# BPQ.net
KiCad netlist of a schematic drawn in Altium Designer
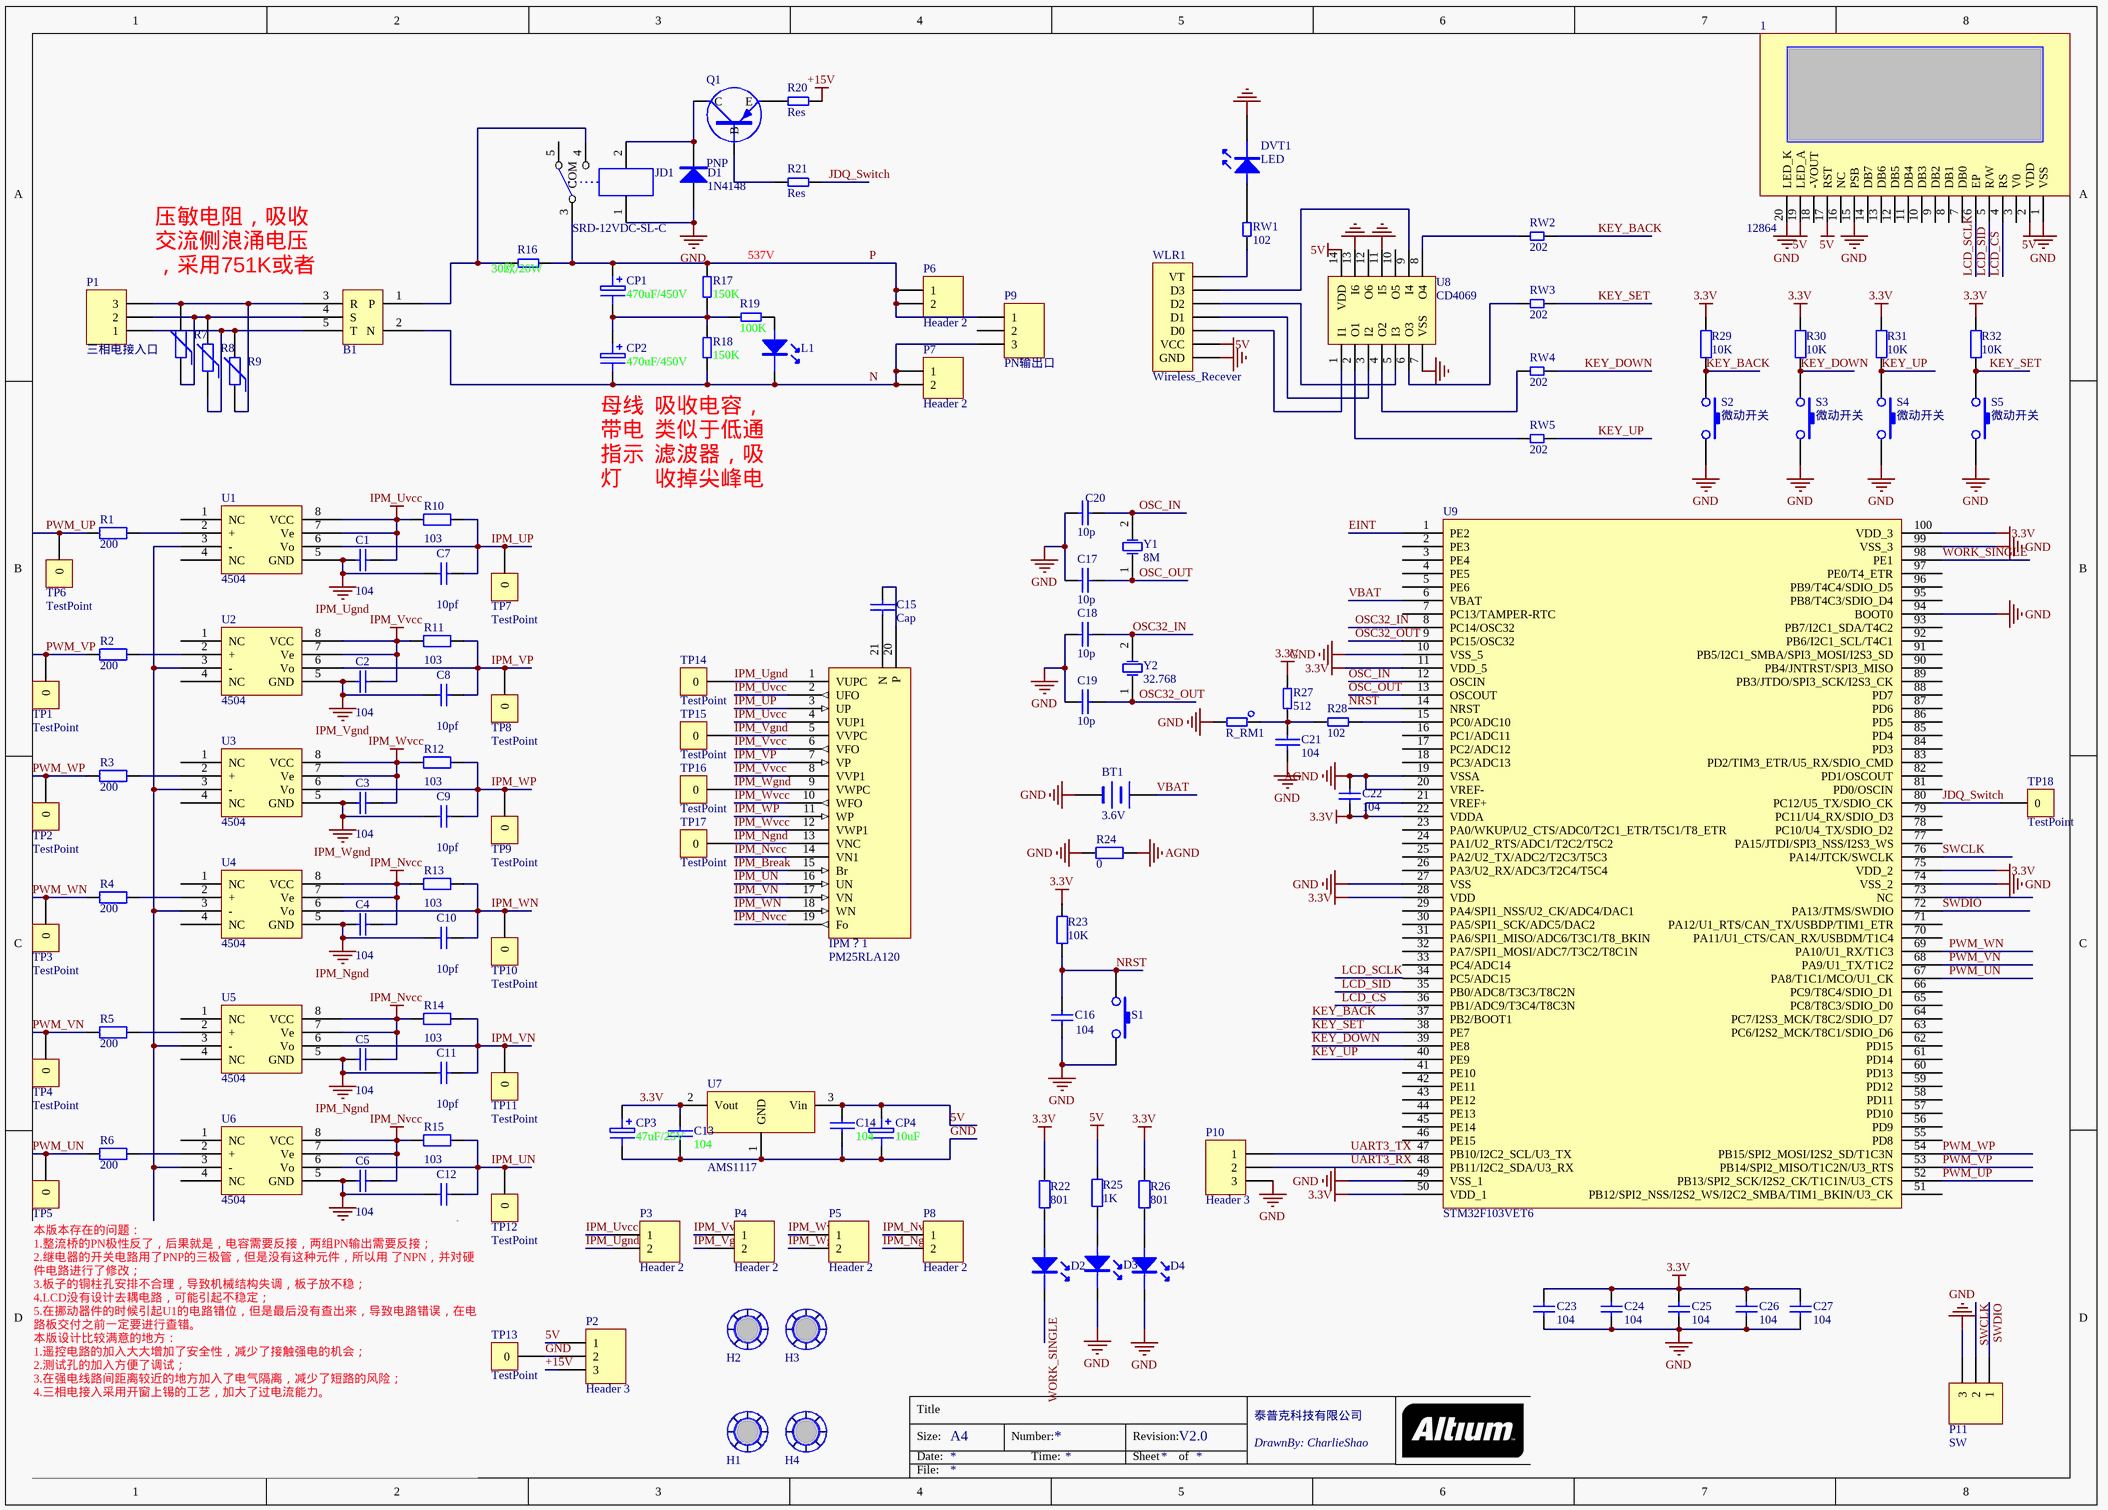
[diagram p0: BPQ.SchDoc]

(export (version "E")
  (design (tool "Eeschema 10.0.6"))
  (components
    (comp (ref "1") (value "12864") (footprint "YX12864B") (libsource (lib "Backup of 杨飞原理库") (part "12864")))
    (comp (ref "B1")
      (value "3BRIDGE")
      (footprint "cloudlib:三相整流桥")
      (libsource (lib "cloudlib") (part "三相整流桥"))
    )
    (comp (ref "BT1")
      (value "3.6V")
      (footprint "CR1220")
      (description "3.6V纽扣电池")
      (libsource (lib "cloudlib") (part "BATTERY"))
    )
    (comp (ref "C1")
      (value "104")
      (footprint "0805C")
      (description "Capacitor")
      (fields (field (name "Comment") "Cap") (field (name "PUBLISHER") "Altium Limited"))
      (libsource (lib "Miscellaneous Devices") (part "Cap"))
    )
    (comp (ref "C2")
      (value "104")
      (footprint "0805C")
      (description "Capacitor")
      (fields (field (name "Comment") "Cap") (field (name "PUBLISHER") "Altium Limited"))
      (libsource (lib "Miscellaneous Devices") (part "Cap"))
    )
    (comp (ref "C3")
      (value "104")
      (footprint "0805C")
      (description "Capacitor")
      (fields (field (name "Comment") "Cap") (field (name "PUBLISHER") "Altium Limited"))
      (libsource (lib "Miscellaneous Devices") (part "Cap"))
    )
    (comp (ref "C4")
      (value "104")
      (footprint "0805C")
      (description "Capacitor")
      (fields (field (name "Comment") "Cap") (field (name "PUBLISHER") "Altium Limited"))
      (libsource (lib "Miscellaneous Devices") (part "Cap"))
    )
    (comp (ref "C5")
      (value "104")
      (footprint "0805C")
      (description "Capacitor")
      (fields (field (name "Comment") "Cap") (field (name "PUBLISHER") "Altium Limited"))
      (libsource (lib "Miscellaneous Devices") (part "Cap"))
    )
    (comp (ref "C6")
      (value "104")
      (footprint "0805C")
      (description "Capacitor")
      (fields (field (name "Comment") "Cap") (field (name "PUBLISHER") "Altium Limited"))
      (libsource (lib "Miscellaneous Devices") (part "Cap"))
    )
    (comp (ref "C7")
      (value "10pf")
      (footprint "0805C")
      (description "Capacitor")
      (fields (field (name "Comment") "Cap") (field (name "PUBLISHER") "Altium Limited"))
      (libsource (lib "Miscellaneous Devices") (part "Cap"))
    )
    (comp (ref "C8")
      (value "10pf")
      (footprint "0805C")
      (description "Capacitor")
      (fields (field (name "Comment") "Cap") (field (name "PUBLISHER") "Altium Limited"))
      (libsource (lib "Miscellaneous Devices") (part "Cap"))
    )
    (comp (ref "C9")
      (value "10pf")
      (footprint "0805C")
      (description "Capacitor")
      (fields (field (name "Comment") "Cap") (field (name "PUBLISHER") "Altium Limited"))
      (libsource (lib "Miscellaneous Devices") (part "Cap"))
    )
    (comp (ref "C10")
      (value "10pf")
      (footprint "0805C")
      (description "Capacitor")
      (fields (field (name "Comment") "Cap") (field (name "PUBLISHER") "Altium Limited"))
      (libsource (lib "Miscellaneous Devices") (part "Cap"))
    )
    (comp (ref "C11")
      (value "10pf")
      (footprint "0805C")
      (description "Capacitor")
      (fields (field (name "Comment") "Cap") (field (name "PUBLISHER") "Altium Limited"))
      (libsource (lib "Miscellaneous Devices") (part "Cap"))
    )
    (comp (ref "C12")
      (value "10pf")
      (footprint "0805C")
      (description "Capacitor")
      (fields (field (name "Comment") "Cap") (field (name "PUBLISHER") "Altium Limited"))
      (libsource (lib "Miscellaneous Devices") (part "Cap"))
    )
    (comp (ref "C13")
      (value "104")
      (footprint "0805C")
      (description "非极性电容")
      (libsource (lib "cloudlib") (part "Cap"))
    )
    (comp (ref "C14")
      (value "104")
      (footprint "0805C")
      (description "非极性电容")
      (libsource (lib "cloudlib") (part "Cap"))
    )
    (comp (ref "C15")
      (value "Cap")
      (footprint "cloudlib:Cap_X")
      (description "非极性电容")
      (libsource (lib "cloudlib") (part "Cap"))
    )
    (comp (ref "C16")
      (value "104")
      (footprint "0805C")
      (description "Capacitor")
      (fields (field (name "PUBLISHER") "Altium Limited"))
      (libsource (lib "Miscellaneous Devices") (part "Cap"))
    )
    (comp (ref "C17")
      (value "10p")
      (footprint "0805C")
      (description "非极性电容")
      (libsource (lib "cloudlib") (part "Cap"))
    )
    (comp (ref "C18")
      (value "10p")
      (footprint "0805C")
      (description "非极性电容")
      (libsource (lib "cloudlib") (part "Cap"))
    )
    (comp (ref "C19")
      (value "10p")
      (footprint "0805C")
      (description "非极性电容")
      (libsource (lib "cloudlib") (part "Cap"))
    )
    (comp (ref "C20")
      (value "10p")
      (footprint "0805C")
      (description "非极性电容")
      (libsource (lib "cloudlib") (part "Cap"))
    )
    (comp (ref "C21")
      (value "104")
      (footprint "0805C")
      (description "非极性电容")
      (libsource (lib "cloudlib") (part "Cap"))
    )
    (comp (ref "C22")
      (value "104")
      (footprint "0805C")
      (description "Capacitor")
      (fields (field (name "PUBLISHER") "Altium Limited"))
      (libsource (lib "Miscellaneous Devices") (part "Cap"))
    )
    (comp (ref "C23")
      (value "104")
      (footprint "0805C")
      (description "Capacitor")
      (fields (field (name "PUBLISHER") "Altium Limited"))
      (libsource (lib "Miscellaneous Devices") (part "Cap"))
    )
    (comp (ref "C24")
      (value "104")
      (footprint "0805C")
      (description "Capacitor")
      (fields (field (name "PUBLISHER") "Altium Limited"))
      (libsource (lib "Miscellaneous Devices") (part "Cap"))
    )
    (comp (ref "C25")
      (value "104")
      (footprint "0805C")
      (description "Capacitor")
      (fields (field (name "PUBLISHER") "Altium Limited"))
      (libsource (lib "Miscellaneous Devices") (part "Cap"))
    )
    (comp (ref "C26")
      (value "104")
      (footprint "0805C")
      (description "Capacitor")
      (fields (field (name "PUBLISHER") "Altium Limited"))
      (libsource (lib "Miscellaneous Devices") (part "Cap"))
    )
    (comp (ref "C27")
      (value "104")
      (footprint "0805C")
      (description "Capacitor")
      (fields (field (name "PUBLISHER") "Altium Limited"))
      (libsource (lib "Miscellaneous Devices") (part "Cap"))
    )
    (comp (ref "CP1")
      (value "470uF/450V")
      (footprint "cloudlib:CAP_35X50")
      (description "极性电容")
      (libsource (lib "cloudlib") (part "Cap_Pol"))
    )
    (comp (ref "CP2")
      (value "470uF/450V")
      (footprint "cloudlib:CAP_35X50")
      (description "极性电容")
      (libsource (lib "cloudlib") (part "Cap_Pol"))
    )
    (comp (ref "CP3")
      (value "47uF/25V")
      (footprint "cloudlib:CAP_6.3X5.4")
      (description "极性电容")
      (libsource (lib "cloudlib") (part "Cap_Pol"))
    )
    (comp (ref "CP4")
      (value "10uF")
      (footprint "cloudlib:CAP_6.3X5.4")
      (description "极性电容")
      (libsource (lib "cloudlib") (part "Cap_Pol"))
    )
    (comp (ref "D1") (value "1N4148") (footprint "cloudlib:Diode_1206") (libsource (lib "*") (part "DIODE2")))
    (comp (ref "D2") (value "LED") (footprint "cloudlib:LED_0805") (libsource (lib "CCDXPLIB") (part "LED")))
    (comp (ref "D3") (value "LED") (footprint "cloudlib:LED_0805") (libsource (lib "CCDXPLIB") (part "LED")))
    (comp (ref "D4") (value "LED") (footprint "cloudlib:LED_0805") (libsource (lib "CCDXPLIB") (part "LED")))
    (comp (ref "DVT1") (value "LED") (footprint "cloudlib:LED_1206") (libsource (lib "*") (part "LED")))
    (comp (ref "H1") (value "铜柱孔") (footprint "HOLE") (libsource (lib "cloudlib") (part "铜柱孔")))
    (comp (ref "H2") (value "铜柱孔") (footprint "HOLE") (libsource (lib "cloudlib") (part "铜柱孔")))
    (comp (ref "H3") (value "铜柱孔") (footprint "HOLE") (libsource (lib "cloudlib") (part "铜柱孔")))
    (comp (ref "H4") (value "铜柱孔") (footprint "HOLE") (libsource (lib "cloudlib") (part "铜柱孔")))
    (comp (ref "IPM？1")
      (value "PM25RLA120")
      (footprint "cloudlib:PM25RLA120")
      (description "三菱IPM模块25A 1200V")
      (libsource (lib "cloudlib") (part "PM25RLA120"))
    )
    (comp (ref "JD1")
      (value "SRD-12VDC-SL-C")
      (footprint "SRD-12VDC-SL-C")
      (description "松乐 10A    12V继电器")
      (libsource (lib "cloudlib") (part "SRD-12VDC-SL-C"))
    )
    (comp (ref "L1")
      (value "LED")
      (footprint "LED_1206")
      (description "发光二极管")
      (libsource (lib "cloudlib") (part "LED"))
    )
    (comp (ref "P1")
      (value "三相电接入口")
      (footprint "cloudlib:30A/300V")
      (description "Header, 3-Pin")
      (fields (field (name "PUBLISHER") "Altium Limited"))
      (libsource (lib "") (part "Header 3_2"))
    )
    (comp (ref "P2")
      (value "Header 3")
      (footprint "HDR1X3")
      (description "Header, 3-Pin")
      (fields (field (name "PUBLISHER") "Altium Limited"))
      (libsource (lib "Miscellaneous Connectors") (part "Header 3"))
    )
    (comp (ref "P3")
      (value "Header 2")
      (footprint "HDR1X2")
      (description "Header, 2-Pin")
      (fields (field (name "PUBLISHER") "Altium Limited"))
      (libsource (lib "Miscellaneous Connectors") (part "Header 2"))
    )
    (comp (ref "P4")
      (value "Header 2")
      (footprint "HDR1X2")
      (description "Header, 2-Pin")
      (fields (field (name "PUBLISHER") "Altium Limited"))
      (libsource (lib "Miscellaneous Connectors") (part "Header 2"))
    )
    (comp (ref "P5")
      (value "Header 2")
      (footprint "HDR1X2")
      (description "Header, 2-Pin")
      (fields (field (name "PUBLISHER") "Altium Limited"))
      (libsource (lib "Miscellaneous Connectors") (part "Header 2"))
    )
    (comp (ref "P6")
      (value "Header 2")
      (footprint "HDR1X2")
      (description "Header, 2-Pin")
      (fields (field (name "PUBLISHER") "Altium Limited"))
      (libsource (lib "Miscellaneous Connectors") (part "Header 2"))
    )
    (comp (ref "P7")
      (value "Header 2")
      (footprint "HDR1X2")
      (description "Header, 2-Pin")
      (fields (field (name "PUBLISHER") "Altium Limited"))
      (libsource (lib "Miscellaneous Connectors") (part "Header 2"))
    )
    (comp (ref "P8")
      (value "Header 2")
      (footprint "HDR1X2")
      (description "Header, 2-Pin")
      (fields (field (name "PUBLISHER") "Altium Limited"))
      (libsource (lib "Miscellaneous Connectors") (part "Header 2"))
    )
    (comp (ref "P9")
      (value "PN输出口")
      (footprint "cloudlib:30A/300V")
      (description "Header, 3-Pin")
      (fields (field (name "PUBLISHER") "Altium Limited"))
      (libsource (lib "Miscellaneous Connectors") (part "Header 3"))
    )
    (comp (ref "P10")
      (value "Header 3")
      (footprint "HDR1X3")
      (description "Header, 3-Pin")
      (fields (field (name "PUBLISHER") "Altium Limited"))
      (libsource (lib "") (part "Header 3_1"))
    )
    (comp (ref "P11")
      (value "SW")
      (footprint "HDR1X3H")
      (description "Header, 3-Pin, Right Angle")
      (fields (field (name "PUBLISHER") "Altium Limited"))
      (libsource (lib "Miscellaneous Connectors") (part "Header 3H"))
    )
    (comp (ref "Q1")
      (value "PNP")
      (footprint "SOT23")
      (description "PNP Transistor")
      (libsource (lib "cloudlib") (part "PNP"))
    )
    (comp (ref "R1")
      (value "200")
      (footprint "0805R")
      (description "Resistor")
      (fields (field (name "Comment") "Res2") (field (name "PUBLISHER") "Altium Limited"))
      (libsource (lib "") (part "Res2_2"))
    )
    (comp (ref "R2")
      (value "200")
      (footprint "0805R")
      (description "Resistor")
      (fields (field (name "Comment") "Res2") (field (name "PUBLISHER") "Altium Limited"))
      (libsource (lib "") (part "Res2_2"))
    )
    (comp (ref "R3")
      (value "200")
      (footprint "0805R")
      (description "Resistor")
      (fields (field (name "Comment") "Res2") (field (name "PUBLISHER") "Altium Limited"))
      (libsource (lib "") (part "Res2_2"))
    )
    (comp (ref "R4")
      (value "200")
      (footprint "0805R")
      (description "Resistor")
      (fields (field (name "Comment") "Res2") (field (name "PUBLISHER") "Altium Limited"))
      (libsource (lib "") (part "Res2_2"))
    )
    (comp (ref "R5")
      (value "200")
      (footprint "0805R")
      (description "Resistor")
      (fields (field (name "Comment") "Res2") (field (name "PUBLISHER") "Altium Limited"))
      (libsource (lib "") (part "Res2_2"))
    )
    (comp (ref "R6")
      (value "200")
      (footprint "0805R")
      (description "Resistor")
      (fields (field (name "Comment") "Res2") (field (name "PUBLISHER") "Altium Limited"))
      (libsource (lib "") (part "Res2_2"))
    )
    (comp (ref "R7")
      (value "Res Varistor")
      (footprint "cloudlib:R_VDR")
      (description "Varistor (Voltage-Sensitive Resistor)")
      (fields (field (name "PUBLISHER") "Altium Limited"))
      (libsource (lib "Miscellaneous Devices") (part "Res Varistor"))
    )
    (comp (ref "R8")
      (value "Res Varistor")
      (footprint "cloudlib:R_VDR")
      (description "Varistor (Voltage-Sensitive Resistor)")
      (fields (field (name "PUBLISHER") "Altium Limited"))
      (libsource (lib "Miscellaneous Devices") (part "Res Varistor"))
    )
    (comp (ref "R9")
      (value "Res Varistor")
      (footprint "cloudlib:R_VDR")
      (description "Varistor (Voltage-Sensitive Resistor)")
      (fields (field (name "PUBLISHER") "Altium Limited"))
      (libsource (lib "Miscellaneous Devices") (part "Res Varistor"))
    )
    (comp (ref "R10")
      (value "103")
      (footprint "0805R")
      (description "Resistor")
      (fields (field (name "Comment") "Res2") (field (name "PUBLISHER") "Altium Limited"))
      (libsource (lib "") (part "Res2_2"))
    )
    (comp (ref "R11")
      (value "103")
      (footprint "0805R")
      (description "Resistor")
      (fields (field (name "Comment") "Res2") (field (name "PUBLISHER") "Altium Limited"))
      (libsource (lib "") (part "Res2_2"))
    )
    (comp (ref "R12")
      (value "103")
      (footprint "0805R")
      (description "Resistor")
      (fields (field (name "Comment") "Res2") (field (name "PUBLISHER") "Altium Limited"))
      (libsource (lib "") (part "Res2_2"))
    )
    (comp (ref "R13")
      (value "103")
      (footprint "0805R")
      (description "Resistor")
      (fields (field (name "Comment") "Res2") (field (name "PUBLISHER") "Altium Limited"))
      (libsource (lib "") (part "Res2_2"))
    )
    (comp (ref "R14")
      (value "103")
      (footprint "0805R")
      (description "Resistor")
      (fields (field (name "Comment") "Res2") (field (name "PUBLISHER") "Altium Limited"))
      (libsource (lib "") (part "Res2_2"))
    )
    (comp (ref "R15")
      (value "103")
      (footprint "0805R")
      (description "Resistor")
      (fields (field (name "Comment") "Res2") (field (name "PUBLISHER") "Altium Limited"))
      (libsource (lib "") (part "Res2_2"))
    )
    (comp (ref "R16")
      (value "30欧/20W")
      (footprint "cloudlib:R_30R/20W")
      (description "电阻")
      (libsource (lib "cloudlib") (part "Res"))
    )
    (comp (ref "R17")
      (value "150K")
      (footprint "myall:AXIAL0.7")
      (description "电阻")
      (libsource (lib "cloudlib") (part "Res"))
    )
    (comp (ref "R18")
      (value "150K")
      (footprint "myall:AXIAL0.7")
      (description "电阻")
      (libsource (lib "cloudlib") (part "Res"))
    )
    (comp (ref "R19")
      (value "100K")
      (footprint "cloudlib:0805R")
      (description "电阻")
      (libsource (lib "cloudlib") (part "Res"))
    )
    (comp (ref "R20")
      (value "Res")
      (footprint "0805R")
      (description "电阻")
      (libsource (lib "cloudlib") (part "Res"))
    )
    (comp (ref "R21")
      (value "Res")
      (footprint "0805R")
      (description "电阻")
      (libsource (lib "cloudlib") (part "Res"))
    )
    (comp (ref "R22")
      (value "801")
      (footprint "0805R")
      (description "Resistor")
      (fields (field (name "PUBLISHER") "Altium Limited"))
      (libsource (lib "") (part "Res2_1"))
    )
    (comp (ref "R23")
      (value "10K")
      (footprint "0805R")
      (description "Resistor")
      (fields (field (name "PUBLISHER") "Altium Limited"))
      (libsource (lib "") (part "Res2_3"))
    )
    (comp (ref "R24")
      (value "0")
      (footprint "0805R")
      (description "Resistor")
      (fields (field (name "PUBLISHER") "Altium Limited"))
      (libsource (lib "Miscellaneous Devices") (part "Res2"))
    )
    (comp (ref "R25")
      (value "1K")
      (footprint "0805R")
      (description "Resistor")
      (fields (field (name "PUBLISHER") "Altium Limited"))
      (libsource (lib "") (part "Res2_1"))
    )
    (comp (ref "R26")
      (value "801")
      (footprint "0805R")
      (description "Resistor")
      (fields (field (name "PUBLISHER") "Altium Limited"))
      (libsource (lib "") (part "Res2_1"))
    )
    (comp (ref "R27")
      (value "512")
      (footprint "0805R")
      (description "电阻")
      (libsource (lib "cloudlib") (part "Res"))
    )
    (comp (ref "R28")
      (value "102")
      (footprint "0805R")
      (description "电阻")
      (libsource (lib "cloudlib") (part "Res"))
    )
    (comp (ref "R29")
      (value "10K")
      (footprint "0805R")
      (description "Resistor")
      (fields (field (name "PUBLISHER") "Altium Limited"))
      (libsource (lib "") (part "Res2_3"))
    )
    (comp (ref "R30")
      (value "10K")
      (footprint "0805R")
      (description "Resistor")
      (fields (field (name "PUBLISHER") "Altium Limited"))
      (libsource (lib "") (part "Res2_3"))
    )
    (comp (ref "R31")
      (value "10K")
      (footprint "0805R")
      (description "Resistor")
      (fields (field (name "PUBLISHER") "Altium Limited"))
      (libsource (lib "") (part "Res2_3"))
    )
    (comp (ref "R32")
      (value "10K")
      (footprint "0805R")
      (description "Resistor")
      (fields (field (name "PUBLISHER") "Altium Limited"))
      (libsource (lib "") (part "Res2_3"))
    )
    (comp (ref "RW1") (value "102") (footprint "0805R") (libsource (lib "*") (part "RES2")))
    (comp (ref "RW2") (value "202") (footprint "0805R") (libsource (lib "*") (part "RES2")))
    (comp (ref "RW3") (value "202") (footprint "0805R") (libsource (lib "*") (part "RES2")))
    (comp (ref "RW4") (value "202") (footprint "0805R") (libsource (lib "*") (part "RES2")))
    (comp (ref "RW5") (value "202") (footprint "0805R") (libsource (lib "*") (part "RES2")))
    (comp (ref "R_RM1")
      (value "热敏电阻")
      (footprint "R_RM")
      (libsource (lib "cloudlib") (part "Res_Temperature"))
    )
    (comp (ref "S1")
      (value "KEY")
      (footprint "cloudlib:SW_PB - 6.5x4.5")
      (libsource (lib "CCDXPLIB") (part "KEY"))
    )
    (comp (ref "S2")
      (value "微动开关")
      (footprint "cloudlib:SW_PB - 6.5x4.5")
      (libsource (lib "开关") (part "微动开关"))
    )
    (comp (ref "S3")
      (value "微动开关")
      (footprint "cloudlib:SW_PB - 6.5x4.5")
      (libsource (lib "开关") (part "微动开关"))
    )
    (comp (ref "S4")
      (value "微动开关")
      (footprint "cloudlib:SW_PB - 6.5x4.5")
      (libsource (lib "开关") (part "微动开关"))
    )
    (comp (ref "S5")
      (value "微动开关")
      (footprint "cloudlib:SW_PB - 6.5x4.5")
      (libsource (lib "开关") (part "微动开关"))
    )
    (comp (ref "TP1")
      (value "TestPoint")
      (footprint "TEST-POINT")
      (libsource (lib "cloudlib") (part "TestPoint"))
    )
    (comp (ref "TP2")
      (value "TestPoint")
      (footprint "TEST-POINT")
      (libsource (lib "cloudlib") (part "TestPoint"))
    )
    (comp (ref "TP3")
      (value "TestPoint")
      (footprint "TEST-POINT")
      (libsource (lib "cloudlib") (part "TestPoint"))
    )
    (comp (ref "TP4")
      (value "TestPoint")
      (footprint "TEST-POINT")
      (libsource (lib "cloudlib") (part "TestPoint"))
    )
    (comp (ref "TP5")
      (value "TestPoint")
      (footprint "TEST-POINT")
      (libsource (lib "cloudlib") (part "TestPoint"))
    )
    (comp (ref "TP6")
      (value "TestPoint")
      (footprint "TEST-POINT")
      (libsource (lib "cloudlib") (part "TestPoint"))
    )
    (comp (ref "TP7")
      (value "TestPoint")
      (footprint "TEST-POINT")
      (libsource (lib "cloudlib") (part "TestPoint"))
    )
    (comp (ref "TP8")
      (value "TestPoint")
      (footprint "TEST-POINT")
      (libsource (lib "cloudlib") (part "TestPoint"))
    )
    (comp (ref "TP9")
      (value "TestPoint")
      (footprint "TEST-POINT")
      (libsource (lib "cloudlib") (part "TestPoint"))
    )
    (comp (ref "TP10")
      (value "TestPoint")
      (footprint "TEST-POINT")
      (libsource (lib "cloudlib") (part "TestPoint"))
    )
    (comp (ref "TP11")
      (value "TestPoint")
      (footprint "TEST-POINT")
      (libsource (lib "cloudlib") (part "TestPoint"))
    )
    (comp (ref "TP12")
      (value "TestPoint")
      (footprint "TEST-POINT")
      (libsource (lib "cloudlib") (part "TestPoint"))
    )
    (comp (ref "TP13") (value "TestPoint") (footprint "TEST-POINT") (libsource (lib "") (part "TestPoint_1")))
    (comp (ref "TP14") (value "TestPoint") (footprint "TEST-POINT") (libsource (lib "") (part "TestPoint_1")))
    (comp (ref "TP15") (value "TestPoint") (footprint "TEST-POINT") (libsource (lib "") (part "TestPoint_1")))
    (comp (ref "TP16") (value "TestPoint") (footprint "TEST-POINT") (libsource (lib "") (part "TestPoint_1")))
    (comp (ref "TP17") (value "TestPoint") (footprint "TEST-POINT") (libsource (lib "") (part "TestPoint_1")))
    (comp (ref "TP18") (value "TestPoint") (footprint "TEST-POINT") (libsource (lib "") (part "TestPoint_2")))
    (comp (ref "U1") (value "4504") (footprint "DIP-8") (libsource (lib "my schematic") (part "4504")))
    (comp (ref "U2") (value "4504") (footprint "DIP-8") (libsource (lib "my schematic") (part "4504")))
    (comp (ref "U3") (value "4504") (footprint "DIP-8") (libsource (lib "my schematic") (part "4504")))
    (comp (ref "U4") (value "4504") (footprint "DIP-8") (libsource (lib "my schematic") (part "4504")))
    (comp (ref "U5") (value "4504") (footprint "DIP-8") (libsource (lib "my schematic") (part "4504")))
    (comp (ref "U6") (value "4504") (footprint "DIP-8") (libsource (lib "my schematic") (part "4504")))
    (comp (ref "U7")
      (value "AMS1117")
      (footprint "SOT223")
      (description "三端稳压器件")
      (libsource (lib "cloudlib") (part "AMS1117"))
    )
    (comp (ref "U8") (value "CD4069") (footprint "SO-14") (libsource (lib "*") (part "CD4069")))
    (comp (ref "U9")
      (value "STM32F103VET6")
      (footprint "cloudlib:LQFP100")
      (libsource (lib "cloudlib") (part "STM32F103VET6"))
    )
    (comp (ref "WLR1")
      (value "Wireless_Recever")
      (footprint "Wireless_Recever")
      (description "Connector")
      (libsource (lib "cloudlib") (part "Wireless_Recever"))
    )
    (comp (ref "Y1")
      (value "8M")
      (footprint "XTAL2")
      (description "Crystal Oscillator")
      (fields (field (name "PUBLISHER") "Altium Limited"))
      (libsource (lib "cloudlib") (part "XTAL"))
    )
    (comp (ref "Y2")
      (value "32.768")
      (footprint "XTAL1")
      (description "Crystal Oscillator")
      (fields (field (name "PUBLISHER") "Altium Limited"))
      (libsource (lib "cloudlib") (part "XTAL"))
    )
  )
  (nets
    (net (code "1") (name "+15V") (class "Default")
      (node (ref "P2") (pin "3") (pinfunction "3_3") (pintype "passive"))
      (node (ref "R20") (pin "2") (pinfunction "2_2") (pintype "passive"))
    )
    (net (code "2") (name "/EINT") (class "Default")
      (node (ref "U9") (pin "1") (pinfunction "PE2_1") (pintype "passive"))
    )
    (net (code "3") (name "/IPM_Break") (class "Default")
      (node (ref "IPM？1") (pin "15") (pinfunction "Br_15") (pintype "input"))
    )
    (net (code "4") (name "/IPM_UN") (class "Default")
      (node (ref "C12") (pin "2") (pinfunction "2_2") (pintype "passive"))
      (node (ref "IPM？1") (pin "16") (pinfunction "UN_16") (pintype "input"))
      (node (ref "R15") (pin "2") (pinfunction "2_2") (pintype "passive"))
      (node (ref "TP12") (pin "0") (pinfunction "0_0") (pintype "passive"))
      (node (ref "U6") (pin "6") (pinfunction "Vo_6") (pintype "passive"))
    )
    (net (code "5") (name "/IPM_UP") (class "Default")
      (node (ref "C7") (pin "2") (pinfunction "2_2") (pintype "passive"))
      (node (ref "IPM？1") (pin "3") (pinfunction "UP_3") (pintype "input"))
      (node (ref "R10") (pin "2") (pinfunction "2_2") (pintype "passive"))
      (node (ref "TP7") (pin "0") (pinfunction "0_0") (pintype "passive"))
      (node (ref "U1") (pin "6") (pinfunction "Vo_6") (pintype "passive"))
    )
    (net (code "6") (name "/IPM_VN") (class "Default")
      (node (ref "C11") (pin "2") (pinfunction "2_2") (pintype "passive"))
      (node (ref "IPM？1") (pin "17") (pinfunction "VN_17") (pintype "input"))
      (node (ref "R14") (pin "2") (pinfunction "2_2") (pintype "passive"))
      (node (ref "TP11") (pin "0") (pinfunction "0_0") (pintype "passive"))
      (node (ref "U5") (pin "6") (pinfunction "Vo_6") (pintype "passive"))
    )
    (net (code "7") (name "/IPM_VP") (class "Default")
      (node (ref "C8") (pin "2") (pinfunction "2_2") (pintype "passive"))
      (node (ref "IPM？1") (pin "7") (pinfunction "VP_7") (pintype "input"))
      (node (ref "R11") (pin "2") (pinfunction "2_2") (pintype "passive"))
      (node (ref "TP8") (pin "0") (pinfunction "0_0") (pintype "passive"))
      (node (ref "U2") (pin "6") (pinfunction "Vo_6") (pintype "passive"))
    )
    (net (code "8") (name "/IPM_WN") (class "Default")
      (node (ref "C10") (pin "2") (pinfunction "2_2") (pintype "passive"))
      (node (ref "IPM？1") (pin "18") (pinfunction "WN_18") (pintype "input"))
      (node (ref "R13") (pin "2") (pinfunction "2_2") (pintype "passive"))
      (node (ref "TP10") (pin "0") (pinfunction "0_0") (pintype "passive"))
      (node (ref "U4") (pin "6") (pinfunction "Vo_6") (pintype "passive"))
    )
    (net (code "9") (name "/IPM_WP") (class "Default")
      (node (ref "C9") (pin "2") (pinfunction "2_2") (pintype "passive"))
      (node (ref "IPM？1") (pin "11") (pinfunction "WP_11") (pintype "input"))
      (node (ref "R12") (pin "2") (pinfunction "2_2") (pintype "passive"))
      (node (ref "TP9") (pin "0") (pinfunction "0_0") (pintype "passive"))
      (node (ref "U3") (pin "6") (pinfunction "Vo_6") (pintype "passive"))
    )
    (net (code "10") (name "/JDQ_Switch") (class "Default")
      (node (ref "R21") (pin "2") (pinfunction "2_2") (pintype "passive"))
      (node (ref "TP18") (pin "0") (pinfunction "0_0") (pintype "passive"))
      (node (ref "U9") (pin "80") (pinfunction "PC12/U5_TX/SDIO_CK_80") (pintype "passive"))
    )
    (net (code "11") (name "/KEY_BACK") (class "Default")
      (node (ref "R29") (pin "1") (pinfunction "1_1") (pintype "passive"))
      (node (ref "RW2") (pin "1") (pinfunction "1_1") (pintype "passive"))
      (node (ref "S2") (pin "1") (pinfunction "1_1") (pintype "passive"))
      (node (ref "U9") (pin "37") (pinfunction "PB2/BOOT1_37") (pintype "passive"))
    )
    (net (code "12") (name "/KEY_DOWN") (class "Default")
      (node (ref "R30") (pin "1") (pinfunction "1_1") (pintype "passive"))
      (node (ref "RW4") (pin "1") (pinfunction "1_1") (pintype "passive"))
      (node (ref "S3") (pin "1") (pinfunction "1_1") (pintype "passive"))
      (node (ref "U9") (pin "39") (pinfunction "PE8_39") (pintype "passive"))
    )
    (net (code "13") (name "/KEY_SET") (class "Default")
      (node (ref "R32") (pin "1") (pinfunction "1_1") (pintype "passive"))
      (node (ref "RW3") (pin "1") (pinfunction "1_1") (pintype "passive"))
      (node (ref "S5") (pin "1") (pinfunction "1_1") (pintype "passive"))
      (node (ref "U9") (pin "38") (pinfunction "PE7_38") (pintype "passive"))
    )
    (net (code "14") (name "/KEY_UP") (class "Default")
      (node (ref "R31") (pin "1") (pinfunction "1_1") (pintype "passive"))
      (node (ref "RW5") (pin "1") (pinfunction "1_1") (pintype "passive"))
      (node (ref "S4") (pin "1") (pinfunction "1_1") (pintype "passive"))
      (node (ref "U9") (pin "40") (pinfunction "PE9_40") (pintype "passive"))
    )
    (net (code "15") (name "/LCD_CS") (class "Default")
      (node (ref "1") (pin "4") (pinfunction "RS_4") (pintype "passive"))
      (node (ref "U9") (pin "36") (pinfunction "PB1/ADC9/T3C4/T8C3N_36") (pintype "passive"))
    )
    (net (code "16") (name "/LCD_SCLK") (class "Default")
      (node (ref "1") (pin "6") (pinfunction "EP_6") (pintype "passive"))
      (node (ref "U9") (pin "34") (pinfunction "PC5/ADC15_34") (pintype "passive"))
    )
    (net (code "17") (name "/LCD_SID") (class "Default")
      (node (ref "1") (pin "5") (pinfunction "R/W_5") (pintype "passive"))
      (node (ref "U9") (pin "35") (pinfunction "PB0/ADC8/T3C3/T8C2N_35") (pintype "passive"))
    )
    (net (code "18") (name "/N") (class "Default")
      (node (ref "B1") (pin "2") (pinfunction "N_2") (pintype "passive"))
      (node (ref "CP2") (pin "2") (pinfunction "2_2") (pintype "passive"))
      (node (ref "L1") (pin "2") (pinfunction "2_2") (pintype "passive"))
      (node (ref "P7") (pin "1") (pinfunction "1_1") (pintype "passive"))
      (node (ref "P7") (pin "2") (pinfunction "2_2") (pintype "passive"))
      (node (ref "P9") (pin "3") (pinfunction "3_3") (pintype "passive"))
      (node (ref "R18") (pin "1") (pinfunction "1_1") (pintype "passive"))
    )
    (net (code "19") (name "/NRST") (class "Default")
      (node (ref "C16") (pin "2") (pinfunction "2_2") (pintype "passive"))
      (node (ref "R23") (pin "1") (pinfunction "1_1") (pintype "passive"))
      (node (ref "S1") (pin "1") (pinfunction "1_1") (pintype "passive"))
      (node (ref "U9") (pin "14") (pinfunction "NRST_14") (pintype "passive"))
    )
    (net (code "20") (name "/OSC32_IN") (class "Default")
      (node (ref "C18") (pin "2") (pinfunction "2_2") (pintype "passive"))
      (node (ref "U9") (pin "8") (pinfunction "PC14/OSC32_8") (pintype "passive"))
      (node (ref "Y2") (pin "2") (pinfunction "OSC2_2") (pintype "passive"))
    )
    (net (code "21") (name "/OSC32_OUT") (class "Default")
      (node (ref "C19") (pin "2") (pinfunction "2_2") (pintype "passive"))
      (node (ref "U9") (pin "9") (pinfunction "PC15/OSC32_9") (pintype "passive"))
      (node (ref "Y2") (pin "1") (pinfunction "OSC1_1") (pintype "passive"))
    )
    (net (code "22") (name "/OSC_IN") (class "Default")
      (node (ref "C20") (pin "2") (pinfunction "2_2") (pintype "passive"))
      (node (ref "U9") (pin "12") (pinfunction "OSCIN_12") (pintype "passive"))
      (node (ref "Y1") (pin "2") (pinfunction "OSC2_2") (pintype "passive"))
    )
    (net (code "23") (name "/OSC_OUT") (class "Default")
      (node (ref "C17") (pin "2") (pinfunction "2_2") (pintype "passive"))
      (node (ref "U9") (pin "13") (pinfunction "OSCOUT_13") (pintype "passive"))
      (node (ref "Y1") (pin "1") (pinfunction "OSC1_1") (pintype "passive"))
    )
    (net (code "24") (name "/P") (class "Default")
      (node (ref "CP1") (pin "1") (pinfunction "1_1") (pintype "passive"))
      (node (ref "JD1") (pin "3") (pinfunction "COM_3") (pintype "passive"))
      (node (ref "P6") (pin "1") (pinfunction "1_1") (pintype "passive"))
      (node (ref "P6") (pin "2") (pinfunction "2_2") (pintype "passive"))
      (node (ref "P9") (pin "1") (pinfunction "1_1") (pintype "passive"))
      (node (ref "R16") (pin "2") (pinfunction "2_2") (pintype "passive"))
      (node (ref "R17") (pin "2") (pinfunction "2_2") (pintype "passive"))
    )
    (net (code "25") (name "/PWM_UN") (class "Default")
      (node (ref "R6") (pin "1") (pinfunction "1_1") (pintype "passive"))
      (node (ref "TP5") (pin "0") (pinfunction "0_0") (pintype "passive"))
      (node (ref "U9") (pin "67") (pinfunction "PA8/T1C1/MCO/U1_CK_67") (pintype "passive"))
    )
    (net (code "26") (name "/PWM_UP") (class "Default")
      (node (ref "R1") (pin "1") (pinfunction "1_1") (pintype "passive"))
      (node (ref "TP6") (pin "0") (pinfunction "0_0") (pintype "passive"))
      (node (ref "U9") (pin "52") (pinfunction "PB13/SPI2_SCK/I2S2_CK/T1C1N/U3_CTS_52") (pintype "passive"))
    )
    (net (code "27") (name "/PWM_VN") (class "Default")
      (node (ref "R5") (pin "1") (pinfunction "1_1") (pintype "passive"))
      (node (ref "TP4") (pin "0") (pinfunction "0_0") (pintype "passive"))
      (node (ref "U9") (pin "68") (pinfunction "PA9/U1_TX/T1C2_68") (pintype "passive"))
    )
    (net (code "28") (name "/PWM_VP") (class "Default")
      (node (ref "R2") (pin "1") (pinfunction "1_1") (pintype "passive"))
      (node (ref "TP1") (pin "0") (pinfunction "0_0") (pintype "passive"))
      (node (ref "U9") (pin "53") (pinfunction "PB14/SPI2_MISO/T1C2N/U3_RTS_53") (pintype "passive"))
    )
    (net (code "29") (name "/PWM_WN") (class "Default")
      (node (ref "R4") (pin "1") (pinfunction "1_1") (pintype "passive"))
      (node (ref "TP3") (pin "0") (pinfunction "0_0") (pintype "passive"))
      (node (ref "U9") (pin "69") (pinfunction "PA10/U1_RX/T1C3_69") (pintype "passive"))
    )
    (net (code "30") (name "/PWM_WP") (class "Default")
      (node (ref "R3") (pin "1") (pinfunction "1_1") (pintype "passive"))
      (node (ref "TP2") (pin "0") (pinfunction "0_0") (pintype "passive"))
      (node (ref "U9") (pin "54") (pinfunction "PB15/SPI2_MOSI/I2S2_SD/T1C3N_54") (pintype "passive"))
    )
    (net (code "31") (name "/SWCLK") (class "Default")
      (node (ref "P11") (pin "2") (pinfunction "2_2") (pintype "passive"))
      (node (ref "U9") (pin "76") (pinfunction "PA14/JTCK/SWCLK_76") (pintype "passive"))
    )
    (net (code "32") (name "/SWDIO") (class "Default")
      (node (ref "P11") (pin "1") (pinfunction "1_1") (pintype "passive"))
      (node (ref "U9") (pin "72") (pinfunction "PA13/JTMS/SWDIO_72") (pintype "passive"))
    )
    (net (code "33") (name "/UART3_RX") (class "Default")
      (node (ref "P10") (pin "2") (pinfunction "2_2") (pintype "passive"))
      (node (ref "U9") (pin "48") (pinfunction "PB11/I2C2_SDA/U3_RX_48") (pintype "passive"))
    )
    (net (code "34") (name "/UART3_TX") (class "Default")
      (node (ref "P10") (pin "1") (pinfunction "1_1") (pintype "passive"))
      (node (ref "U9") (pin "47") (pinfunction "PB10/I2C2_SCL/U3_TX_47") (pintype "passive"))
    )
    (net (code "35") (name "/VBAT") (class "Default")
      (node (ref "BT1") (pin "1") (pinfunction "+_1") (pintype "passive"))
      (node (ref "U9") (pin "6") (pinfunction "VBAT_6") (pintype "passive"))
    )
    (net (code "36") (name "/WORK_SINGLE") (class "Default")
      (node (ref "D2") (pin "2") (pinfunction "2_2") (pintype "passive"))
      (node (ref "U9") (pin "98") (pinfunction "PE1_98") (pintype "passive"))
    )
    (net (code "37") (name "3.3V") (class "Default")
      (node (ref "C13") (pin "2") (pinfunction "2_2") (pintype "passive"))
      (node (ref "C22") (pin "2") (pinfunction "2_2") (pintype "passive"))
      (node (ref "C23") (pin "1") (pinfunction "1_1") (pintype "passive"))
      (node (ref "C24") (pin "1") (pinfunction "1_1") (pintype "passive"))
      (node (ref "C25") (pin "1") (pinfunction "1_1") (pintype "passive"))
      (node (ref "C26") (pin "1") (pinfunction "1_1") (pintype "passive"))
      (node (ref "C27") (pin "1") (pinfunction "1_1") (pintype "passive"))
      (node (ref "CP3") (pin "1") (pinfunction "1_1") (pintype "passive"))
      (node (ref "R22") (pin "1") (pinfunction "1_1") (pintype "passive"))
      (node (ref "R23") (pin "2") (pinfunction "2_2") (pintype "passive"))
      (node (ref "R26") (pin "1") (pinfunction "1_1") (pintype "passive"))
      (node (ref "R27") (pin "1") (pinfunction "1_1") (pintype "passive"))
      (node (ref "R29") (pin "2") (pinfunction "2_2") (pintype "passive"))
      (node (ref "R30") (pin "2") (pinfunction "2_2") (pintype "passive"))
      (node (ref "R31") (pin "2") (pinfunction "2_2") (pintype "passive"))
      (node (ref "R32") (pin "2") (pinfunction "2_2") (pintype "passive"))
      (node (ref "U7") (pin "2") (pinfunction "Vout_2") (pintype "passive"))
      (node (ref "U9") (pin "100") (pinfunction "VDD_3_100") (pintype "passive"))
      (node (ref "U9") (pin "11") (pinfunction "VDD_5_11") (pintype "passive"))
      (node (ref "U9") (pin "21") (pinfunction "VREF+_21") (pintype "passive"))
      (node (ref "U9") (pin "22") (pinfunction "VDDA_22") (pintype "passive"))
      (node (ref "U9") (pin "28") (pinfunction "VDD_28") (pintype "passive"))
      (node (ref "U9") (pin "50") (pinfunction "VDD_1_50") (pintype "passive"))
      (node (ref "U9") (pin "75") (pinfunction "VDD_2_75") (pintype "passive"))
    )
    (net (code "38") (name "5V") (class "Default")
      (node (ref "1") (pin "17") (pinfunction "RST_17") (pintype "passive"))
      (node (ref "1") (pin "19") (pinfunction "LED_A_19") (pintype "passive"))
      (node (ref "1") (pin "2") (pinfunction "VDD_2") (pintype "passive"))
      (node (ref "C14") (pin "2") (pinfunction "2_2") (pintype "passive"))
      (node (ref "CP4") (pin "1") (pinfunction "1_1") (pintype "passive"))
      (node (ref "P2") (pin "1") (pinfunction "1_1") (pintype "passive"))
      (node (ref "R25") (pin "1") (pinfunction "1_1") (pintype "passive"))
      (node (ref "U7") (pin "3") (pinfunction "Vin_3") (pintype "passive"))
      (node (ref "U8") (pin "14") (pinfunction "VDD_14") (pintype "passive"))
      (node (ref "WLR1") (pin "2") (pinfunction "VCC_2") (pintype "passive"))
    )
    (net (code "39") (name "AGND") (class "Default")
      (node (ref "C22") (pin "1") (pinfunction "1_1") (pintype "passive"))
      (node (ref "R24") (pin "1") (pinfunction "1_1") (pintype "passive"))
      (node (ref "U9") (pin "19") (pinfunction "VSSA_19") (pintype "passive"))
      (node (ref "U9") (pin "20") (pinfunction "VREF-_20") (pintype "passive"))
    )
    (net (code "40") (name "GND") (class "Default")
      (node (ref "1") (pin "1") (pinfunction "VSS_1") (pintype "passive"))
      (node (ref "1") (pin "15") (pinfunction "PSB_15") (pintype "passive"))
      (node (ref "1") (pin "20") (pinfunction "LED_K_20") (pintype "passive"))
      (node (ref "BT1") (pin "2") (pinfunction "-_2") (pintype "passive"))
      (node (ref "C13") (pin "1") (pinfunction "1_1") (pintype "passive"))
      (node (ref "C14") (pin "1") (pinfunction "1_1") (pintype "passive"))
      (node (ref "C16") (pin "1") (pinfunction "1_1") (pintype "passive"))
      (node (ref "C17") (pin "1") (pinfunction "1_1") (pintype "passive"))
      (node (ref "C18") (pin "1") (pinfunction "1_1") (pintype "passive"))
      (node (ref "C19") (pin "1") (pinfunction "1_1") (pintype "passive"))
      (node (ref "C20") (pin "1") (pinfunction "1_1") (pintype "passive"))
      (node (ref "C21") (pin "1") (pinfunction "1_1") (pintype "passive"))
      (node (ref "C23") (pin "2") (pinfunction "2_2") (pintype "passive"))
      (node (ref "C24") (pin "2") (pinfunction "2_2") (pintype "passive"))
      (node (ref "C25") (pin "2") (pinfunction "2_2") (pintype "passive"))
      (node (ref "C26") (pin "2") (pinfunction "2_2") (pintype "passive"))
      (node (ref "C27") (pin "2") (pinfunction "2_2") (pintype "passive"))
      (node (ref "CP3") (pin "2") (pinfunction "2_2") (pintype "passive"))
      (node (ref "CP4") (pin "2") (pinfunction "2_2") (pintype "passive"))
      (node (ref "D1") (pin "1") (pinfunction "1_1") (pintype "passive"))
      (node (ref "D3") (pin "2") (pinfunction "2_2") (pintype "passive"))
      (node (ref "D4") (pin "2") (pinfunction "2_2") (pintype "passive"))
      (node (ref "DVT1") (pin "2") (pinfunction "2_2") (pintype "passive"))
      (node (ref "JD1") (pin "1") (pinfunction "1_1") (pintype "passive"))
      (node (ref "P10") (pin "3") (pinfunction "3_3") (pintype "passive"))
      (node (ref "P11") (pin "3") (pinfunction "3_3") (pintype "passive"))
      (node (ref "P2") (pin "2") (pinfunction "2_2") (pintype "passive"))
      (node (ref "R24") (pin "2") (pinfunction "2_2") (pintype "passive"))
      (node (ref "R_RM1") (pin "1") (pinfunction "1_1") (pintype "passive"))
      (node (ref "S1") (pin "2") (pinfunction "2_2") (pintype "passive"))
      (node (ref "S2") (pin "2") (pinfunction "2_2") (pintype "passive"))
      (node (ref "S3") (pin "2") (pinfunction "2_2") (pintype "passive"))
      (node (ref "S4") (pin "2") (pinfunction "2_2") (pintype "passive"))
      (node (ref "S5") (pin "2") (pinfunction "2_2") (pintype "passive"))
      (node (ref "TP13") (pin "0") (pinfunction "0_0") (pintype "passive"))
      (node (ref "U1") (pin "3") (pinfunction "-_3") (pintype "passive"))
      (node (ref "U2") (pin "3") (pinfunction "-_3") (pintype "passive"))
      (node (ref "U3") (pin "3") (pinfunction "-_3") (pintype "passive"))
      (node (ref "U4") (pin "3") (pinfunction "-_3") (pintype "passive"))
      (node (ref "U5") (pin "3") (pinfunction "-_3") (pintype "passive"))
      (node (ref "U6") (pin "3") (pinfunction "-_3") (pintype "passive"))
      (node (ref "U7") (pin "1") (pinfunction "GND_1") (pintype "passive"))
      (node (ref "U8") (pin "11") (pinfunction "I5_11") (pintype "passive"))
      (node (ref "U8") (pin "13") (pinfunction "I6_13") (pintype "passive"))
      (node (ref "U8") (pin "7") (pinfunction "VSS_7") (pintype "passive"))
      (node (ref "U9") (pin "10") (pinfunction "VSS_5_10") (pintype "passive"))
      (node (ref "U9") (pin "27") (pinfunction "VSS_27") (pintype "passive"))
      (node (ref "U9") (pin "49") (pinfunction "VSS_1_49") (pintype "passive"))
      (node (ref "U9") (pin "74") (pinfunction "VSS_2_74") (pintype "passive"))
      (node (ref "U9") (pin "94") (pinfunction "BOOT0_94") (pintype "passive"))
      (node (ref "U9") (pin "99") (pinfunction "VSS_3_99") (pintype "passive"))
      (node (ref "WLR1") (pin "1") (pinfunction "GND_1") (pintype "passive"))
    )
    (net (code "41") (name "IPM_Ngnd") (class "Default")
      (node (ref "C10") (pin "1") (pinfunction "1_1") (pintype "passive"))
      (node (ref "C11") (pin "1") (pinfunction "1_1") (pintype "passive"))
      (node (ref "C12") (pin "1") (pinfunction "1_1") (pintype "passive"))
      (node (ref "C4") (pin "1") (pinfunction "1_1") (pintype "passive"))
      (node (ref "C5") (pin "1") (pinfunction "1_1") (pintype "passive"))
      (node (ref "C6") (pin "1") (pinfunction "1_1") (pintype "passive"))
      (node (ref "IPM？1") (pin "13") (pinfunction "VNC_13") (pintype "passive"))
      (node (ref "P8") (pin "2") (pinfunction "2_2") (pintype "passive"))
      (node (ref "TP17") (pin "0") (pinfunction "0_0") (pintype "passive"))
      (node (ref "U4") (pin "5") (pinfunction "GND_5") (pintype "passive"))
      (node (ref "U5") (pin "5") (pinfunction "GND_5") (pintype "passive"))
      (node (ref "U6") (pin "5") (pinfunction "GND_5") (pintype "passive"))
    )
    (net (code "42") (name "IPM_Nvcc") (class "Default")
      (node (ref "C4") (pin "2") (pinfunction "2_2") (pintype "passive"))
      (node (ref "C5") (pin "2") (pinfunction "2_2") (pintype "passive"))
      (node (ref "C6") (pin "2") (pinfunction "2_2") (pintype "passive"))
      (node (ref "IPM？1") (pin "14") (pinfunction "VN1_14") (pintype "passive"))
      (node (ref "IPM？1") (pin "19") (pinfunction "Fo_19") (pintype "output"))
      (node (ref "P8") (pin "1") (pinfunction "1_1") (pintype "passive"))
      (node (ref "R13") (pin "1") (pinfunction "1_1") (pintype "passive"))
      (node (ref "R14") (pin "1") (pinfunction "1_1") (pintype "passive"))
      (node (ref "R15") (pin "1") (pinfunction "1_1") (pintype "passive"))
      (node (ref "U4") (pin "7") (pinfunction "Ve_7") (pintype "passive"))
      (node (ref "U4") (pin "8") (pinfunction "VCC_8") (pintype "passive"))
      (node (ref "U5") (pin "7") (pinfunction "Ve_7") (pintype "passive"))
      (node (ref "U5") (pin "8") (pinfunction "VCC_8") (pintype "passive"))
      (node (ref "U6") (pin "7") (pinfunction "Ve_7") (pintype "passive"))
      (node (ref "U6") (pin "8") (pinfunction "VCC_8") (pintype "passive"))
    )
    (net (code "43") (name "IPM_Ugnd") (class "Default")
      (node (ref "C1") (pin "1") (pinfunction "1_1") (pintype "passive"))
      (node (ref "C7") (pin "1") (pinfunction "1_1") (pintype "passive"))
      (node (ref "IPM？1") (pin "1") (pinfunction "VUPC_1") (pintype "power_in"))
      (node (ref "P3") (pin "2") (pinfunction "2_2") (pintype "passive"))
      (node (ref "TP14") (pin "0") (pinfunction "0_0") (pintype "passive"))
      (node (ref "U1") (pin "5") (pinfunction "GND_5") (pintype "passive"))
    )
    (net (code "44") (name "IPM_Uvcc") (class "Default")
      (node (ref "C1") (pin "2") (pinfunction "2_2") (pintype "passive"))
      (node (ref "IPM？1") (pin "2") (pinfunction "UFO_2") (pintype "output"))
      (node (ref "IPM？1") (pin "4") (pinfunction "VUP1_4") (pintype "power_in"))
      (node (ref "P3") (pin "1") (pinfunction "1_1") (pintype "passive"))
      (node (ref "R10") (pin "1") (pinfunction "1_1") (pintype "passive"))
      (node (ref "U1") (pin "7") (pinfunction "Ve_7") (pintype "passive"))
      (node (ref "U1") (pin "8") (pinfunction "VCC_8") (pintype "passive"))
    )
    (net (code "45") (name "IPM_Vgnd") (class "Default")
      (node (ref "C2") (pin "1") (pinfunction "1_1") (pintype "passive"))
      (node (ref "C8") (pin "1") (pinfunction "1_1") (pintype "passive"))
      (node (ref "IPM？1") (pin "5") (pinfunction "VVPC_5") (pintype "power_in"))
      (node (ref "P4") (pin "2") (pinfunction "2_2") (pintype "passive"))
      (node (ref "TP15") (pin "0") (pinfunction "0_0") (pintype "passive"))
      (node (ref "U2") (pin "5") (pinfunction "GND_5") (pintype "passive"))
    )
    (net (code "46") (name "IPM_Vvcc") (class "Default")
      (node (ref "C2") (pin "2") (pinfunction "2_2") (pintype "passive"))
      (node (ref "IPM？1") (pin "6") (pinfunction "VFO_6") (pintype "output"))
      (node (ref "IPM？1") (pin "8") (pinfunction "VVP1_8") (pintype "power_in"))
      (node (ref "P4") (pin "1") (pinfunction "1_1") (pintype "passive"))
      (node (ref "R11") (pin "1") (pinfunction "1_1") (pintype "passive"))
      (node (ref "U2") (pin "7") (pinfunction "Ve_7") (pintype "passive"))
      (node (ref "U2") (pin "8") (pinfunction "VCC_8") (pintype "passive"))
    )
    (net (code "47") (name "IPM_Wgnd") (class "Default")
      (node (ref "C3") (pin "1") (pinfunction "1_1") (pintype "passive"))
      (node (ref "C9") (pin "1") (pinfunction "1_1") (pintype "passive"))
      (node (ref "IPM？1") (pin "9") (pinfunction "VWPC_9") (pintype "power_in"))
      (node (ref "P5") (pin "2") (pinfunction "2_2") (pintype "passive"))
      (node (ref "TP16") (pin "0") (pinfunction "0_0") (pintype "passive"))
      (node (ref "U3") (pin "5") (pinfunction "GND_5") (pintype "passive"))
    )
    (net (code "48") (name "IPM_Wvcc") (class "Default")
      (node (ref "C3") (pin "2") (pinfunction "2_2") (pintype "passive"))
      (node (ref "IPM？1") (pin "10") (pinfunction "WFO_10") (pintype "output"))
      (node (ref "IPM？1") (pin "12") (pinfunction "VWP1_12") (pintype "passive"))
      (node (ref "P5") (pin "1") (pinfunction "1_1") (pintype "passive"))
      (node (ref "R12") (pin "1") (pinfunction "1_1") (pintype "passive"))
      (node (ref "U3") (pin "7") (pinfunction "Ve_7") (pintype "passive"))
      (node (ref "U3") (pin "8") (pinfunction "VCC_8") (pintype "passive"))
    )
    (net (code "49") (name "Net-(B1-P)") (class "Default")
      (node (ref "B1") (pin "1") (pinfunction "P_1") (pintype "passive"))
      (node (ref "JD1") (pin "4") (pinfunction "4_4") (pintype "passive"))
      (node (ref "R16") (pin "1") (pinfunction "1_1") (pintype "passive"))
    )
    (net (code "50") (name "Net-(B1-R)") (class "Default")
      (node (ref "B1") (pin "3") (pinfunction "R_3") (pintype "passive"))
      (node (ref "P1") (pin "3") (pinfunction "3_3") (pintype "passive"))
      (node (ref "R7") (pin "2") (pinfunction "2_2") (pintype "passive"))
      (node (ref "R9") (pin "1") (pinfunction "1_1") (pintype "passive"))
    )
    (net (code "51") (name "Net-(B1-S)") (class "Default")
      (node (ref "B1") (pin "4") (pinfunction "S_4") (pintype "passive"))
      (node (ref "P1") (pin "2") (pinfunction "2_2") (pintype "passive"))
      (node (ref "R7") (pin "1") (pinfunction "1_1") (pintype "passive"))
      (node (ref "R8") (pin "2") (pinfunction "2_2") (pintype "passive"))
    )
    (net (code "52") (name "Net-(B1-T)") (class "Default")
      (node (ref "B1") (pin "5") (pinfunction "T_5") (pintype "passive"))
      (node (ref "P1") (pin "1") (pinfunction "1_1") (pintype "passive"))
      (node (ref "R8") (pin "1") (pinfunction "1_1") (pintype "passive"))
      (node (ref "R9") (pin "2") (pinfunction "2_2") (pintype "passive"))
    )
    (net (code "53") (name "Net-(C21-Pad2)") (class "Default")
      (node (ref "C21") (pin "2") (pinfunction "2_2") (pintype "passive"))
      (node (ref "R27") (pin "2") (pinfunction "2_2") (pintype "passive"))
      (node (ref "R28") (pin "2") (pinfunction "2_2") (pintype "passive"))
      (node (ref "R_RM1") (pin "2") (pinfunction "2_2") (pintype "passive"))
    )
    (net (code "54") (name "Net-(CP1-Pad2)") (class "Default")
      (node (ref "CP1") (pin "2") (pinfunction "2_2") (pintype "passive"))
      (node (ref "CP2") (pin "1") (pinfunction "1_1") (pintype "passive"))
      (node (ref "R17") (pin "1") (pinfunction "1_1") (pintype "passive"))
      (node (ref "R18") (pin "2") (pinfunction "2_2") (pintype "passive"))
      (node (ref "R19") (pin "2") (pinfunction "2_2") (pintype "passive"))
    )
    (net (code "55") (name "Net-(D1-Pad2)") (class "Default")
      (node (ref "D1") (pin "2") (pinfunction "2_2") (pintype "passive"))
      (node (ref "JD1") (pin "2") (pinfunction "2_2") (pintype "passive"))
      (node (ref "Q1") (pin "C") (pinfunction "C_C") (pintype "passive"))
    )
    (net (code "56") (name "Net-(D2-Pad1)") (class "Default")
      (node (ref "D2") (pin "1") (pinfunction "1_1") (pintype "passive"))
      (node (ref "R22") (pin "2") (pinfunction "2_2") (pintype "passive"))
    )
    (net (code "57") (name "Net-(D3-Pad1)") (class "Default")
      (node (ref "D3") (pin "1") (pinfunction "1_1") (pintype "passive"))
      (node (ref "R25") (pin "2") (pinfunction "2_2") (pintype "passive"))
    )
    (net (code "58") (name "Net-(D4-Pad1)") (class "Default")
      (node (ref "D4") (pin "1") (pinfunction "1_1") (pintype "passive"))
      (node (ref "R26") (pin "2") (pinfunction "2_2") (pintype "passive"))
    )
    (net (code "59") (name "Net-(DVT1-Pad1)") (class "Default")
      (node (ref "DVT1") (pin "1") (pinfunction "1_1") (pintype "passive"))
      (node (ref "RW1") (pin "2") (pinfunction "2_2") (pintype "passive"))
    )
    (net (code "60") (name "Net-(IPM？1-N)") (class "Default")
      (node (ref "C15") (pin "2") (pinfunction "2_2") (pintype "passive"))
      (node (ref "IPM？1") (pin "21") (pinfunction "N_21") (pintype "passive"))
    )
    (net (code "61") (name "Net-(IPM？1-P)") (class "Default")
      (node (ref "C15") (pin "1") (pinfunction "1_1") (pintype "passive"))
      (node (ref "IPM？1") (pin "20") (pinfunction "P_20") (pintype "passive"))
    )
    (net (code "62") (name "Net-(L1-Pad1)") (class "Default")
      (node (ref "L1") (pin "1") (pinfunction "1_1") (pintype "passive"))
      (node (ref "R19") (pin "1") (pinfunction "1_1") (pintype "passive"))
    )
    (net (code "63") (name "Net-(Q1-PadB)") (class "Default")
      (node (ref "Q1") (pin "B") (pinfunction "B_B") (pintype "passive"))
      (node (ref "R21") (pin "1") (pinfunction "1_1") (pintype "passive"))
    )
    (net (code "64") (name "Net-(Q1-PadE)") (class "Default")
      (node (ref "Q1") (pin "E") (pinfunction "E_E") (pintype "passive"))
      (node (ref "R20") (pin "1") (pinfunction "1_1") (pintype "passive"))
    )
    (net (code "65") (name "Net-(U1-+)") (class "Default")
      (node (ref "R1") (pin "2") (pinfunction "2_2") (pintype "passive"))
      (node (ref "U1") (pin "2") (pinfunction "+_2") (pintype "passive"))
    )
    (net (code "66") (name "Net-(U2-+)") (class "Default")
      (node (ref "R2") (pin "2") (pinfunction "2_2") (pintype "passive"))
      (node (ref "U2") (pin "2") (pinfunction "+_2") (pintype "passive"))
    )
    (net (code "67") (name "Net-(U3-+)") (class "Default")
      (node (ref "R3") (pin "2") (pinfunction "2_2") (pintype "passive"))
      (node (ref "U3") (pin "2") (pinfunction "+_2") (pintype "passive"))
    )
    (net (code "68") (name "Net-(U4-+)") (class "Default")
      (node (ref "R4") (pin "2") (pinfunction "2_2") (pintype "passive"))
      (node (ref "U4") (pin "2") (pinfunction "+_2") (pintype "passive"))
    )
    (net (code "69") (name "Net-(U5-+)") (class "Default")
      (node (ref "R5") (pin "2") (pinfunction "2_2") (pintype "passive"))
      (node (ref "U5") (pin "2") (pinfunction "+_2") (pintype "passive"))
    )
    (net (code "70") (name "Net-(U6-+)") (class "Default")
      (node (ref "R6") (pin "2") (pinfunction "2_2") (pintype "passive"))
      (node (ref "U6") (pin "2") (pinfunction "+_2") (pintype "passive"))
    )
    (net (code "71") (name "Net-(U8-I1)") (class "Default")
      (node (ref "U8") (pin "1") (pinfunction "I1_1") (pintype "passive"))
      (node (ref "WLR1") (pin "3") (pinfunction "D0_3") (pintype "passive"))
    )
    (net (code "72") (name "Net-(U8-I2)") (class "Default")
      (node (ref "U8") (pin "3") (pinfunction "I2_3") (pintype "passive"))
      (node (ref "WLR1") (pin "4") (pinfunction "D1_4") (pintype "passive"))
    )
    (net (code "73") (name "Net-(U8-I3)") (class "Default")
      (node (ref "U8") (pin "5") (pinfunction "I3_5") (pintype "passive"))
      (node (ref "WLR1") (pin "5") (pinfunction "D2_5") (pintype "passive"))
    )
    (net (code "74") (name "Net-(U8-I4)") (class "Default")
      (node (ref "U8") (pin "9") (pinfunction "I4_9") (pintype "passive"))
      (node (ref "WLR1") (pin "6") (pinfunction "D3_6") (pintype "passive"))
    )
    (net (code "75") (name "Net-(U8-O1)") (class "Default")
      (node (ref "RW5") (pin "2") (pinfunction "2_2") (pintype "passive"))
      (node (ref "U8") (pin "2") (pinfunction "O1_2") (pintype "passive"))
    )
    (net (code "76") (name "Net-(U8-O2)") (class "Default")
      (node (ref "RW4") (pin "2") (pinfunction "2_2") (pintype "passive"))
      (node (ref "U8") (pin "4") (pinfunction "O2_4") (pintype "passive"))
    )
    (net (code "77") (name "Net-(U8-O3)") (class "Default")
      (node (ref "RW3") (pin "2") (pinfunction "2_2") (pintype "passive"))
      (node (ref "U8") (pin "6") (pinfunction "O3_6") (pintype "passive"))
    )
    (net (code "78") (name "Net-(U8-O4)") (class "Default")
      (node (ref "RW2") (pin "2") (pinfunction "2_2") (pintype "passive"))
      (node (ref "U8") (pin "8") (pinfunction "O4_8") (pintype "passive"))
    )
    (net (code "79") (name "Net-(U9-PC0{slash}ADC10)") (class "Default")
      (node (ref "R28") (pin "1") (pinfunction "1_1") (pintype "passive"))
      (node (ref "U9") (pin "15") (pinfunction "PC0/ADC10_15") (pintype "passive"))
    )
    (net (code "80") (name "Net-(WLR1-VT)") (class "Default")
      (node (ref "RW1") (pin "1") (pinfunction "1_1") (pintype "passive"))
      (node (ref "WLR1") (pin "7") (pinfunction "VT_7") (pintype "passive"))
    )
    (net (code "81") (name "unconnected-(1--VOUT-Pad18)") (class "Default")
      (node (ref "1") (pin "18") (pinfunction "-VOUT_18") (pintype "passive"))
    )
    (net (code "82") (name "unconnected-(1-DB0-Pad7)") (class "Default")
      (node (ref "1") (pin "7") (pinfunction "DB0_7") (pintype "passive"))
    )
    (net (code "83") (name "unconnected-(1-DB1-Pad8)") (class "Default")
      (node (ref "1") (pin "8") (pinfunction "DB1_8") (pintype "passive"))
    )
    (net (code "84") (name "unconnected-(1-DB2-Pad9)") (class "Default")
      (node (ref "1") (pin "9") (pinfunction "DB2_9") (pintype "passive"))
    )
    (net (code "85") (name "unconnected-(1-DB3-Pad10)") (class "Default")
      (node (ref "1") (pin "10") (pinfunction "DB3_10") (pintype "passive"))
    )
    (net (code "86") (name "unconnected-(1-DB4-Pad11)") (class "Default")
      (node (ref "1") (pin "11") (pinfunction "DB4_11") (pintype "passive"))
    )
    (net (code "87") (name "unconnected-(1-DB5-Pad12)") (class "Default")
      (node (ref "1") (pin "12") (pinfunction "DB5_12") (pintype "passive"))
    )
    (net (code "88") (name "unconnected-(1-DB6-Pad13)") (class "Default")
      (node (ref "1") (pin "13") (pinfunction "DB6_13") (pintype "passive"))
    )
    (net (code "89") (name "unconnected-(1-DB7-Pad14)") (class "Default")
      (node (ref "1") (pin "14") (pinfunction "DB7_14") (pintype "passive"))
    )
    (net (code "90") (name "unconnected-(1-NC-Pad16)") (class "Default")
      (node (ref "1") (pin "16") (pinfunction "NC_16") (pintype "passive"))
    )
    (net (code "91") (name "unconnected-(1-V0-Pad3)") (class "Default")
      (node (ref "1") (pin "3") (pinfunction "V0_3") (pintype "passive"))
    )
    (net (code "92") (name "unconnected-(H1-Pad0)") (class "Default")
      (node (ref "H1") (pin "0") (pinfunction "0_0") (pintype "passive"))
    )
    (net (code "93") (name "unconnected-(H1-Pad0)_1") (class "Default")
      (node (ref "H1") (pin "0") (pinfunction "0_0") (pintype "passive"))
    )
    (net (code "94") (name "unconnected-(H2-Pad0)") (class "Default")
      (node (ref "H2") (pin "0") (pinfunction "0_0") (pintype "passive"))
    )
    (net (code "95") (name "unconnected-(H2-Pad0)_1") (class "Default")
      (node (ref "H2") (pin "0") (pinfunction "0_0") (pintype "passive"))
    )
    (net (code "96") (name "unconnected-(H3-Pad0)") (class "Default")
      (node (ref "H3") (pin "0") (pinfunction "0_0") (pintype "passive"))
    )
    (net (code "97") (name "unconnected-(H3-Pad0)_1") (class "Default")
      (node (ref "H3") (pin "0") (pinfunction "0_0") (pintype "passive"))
    )
    (net (code "98") (name "unconnected-(H4-Pad0)") (class "Default")
      (node (ref "H4") (pin "0") (pinfunction "0_0") (pintype "passive"))
    )
    (net (code "99") (name "unconnected-(H4-Pad0)_1") (class "Default")
      (node (ref "H4") (pin "0") (pinfunction "0_0") (pintype "passive"))
    )
    (net (code "100") (name "unconnected-(JD1-Pad5)") (class "Default")
      (node (ref "JD1") (pin "5") (pinfunction "5_5") (pintype "passive"))
    )
    (net (code "101") (name "unconnected-(P9-Pad2)") (class "Default")
      (node (ref "P9") (pin "2") (pinfunction "2_2") (pintype "passive"))
    )
    (net (code "102") (name "unconnected-(U1-NC-Pad1)") (class "Default")
      (node (ref "U1") (pin "1") (pinfunction "NC_1") (pintype "passive"))
    )
    (net (code "103") (name "unconnected-(U1-NC-Pad4)") (class "Default")
      (node (ref "U1") (pin "4") (pinfunction "NC_4") (pintype "passive"))
    )
    (net (code "104") (name "unconnected-(U2-NC-Pad1)") (class "Default")
      (node (ref "U2") (pin "1") (pinfunction "NC_1") (pintype "passive"))
    )
    (net (code "105") (name "unconnected-(U2-NC-Pad4)") (class "Default")
      (node (ref "U2") (pin "4") (pinfunction "NC_4") (pintype "passive"))
    )
    (net (code "106") (name "unconnected-(U3-NC-Pad1)") (class "Default")
      (node (ref "U3") (pin "1") (pinfunction "NC_1") (pintype "passive"))
    )
    (net (code "107") (name "unconnected-(U3-NC-Pad4)") (class "Default")
      (node (ref "U3") (pin "4") (pinfunction "NC_4") (pintype "passive"))
    )
    (net (code "108") (name "unconnected-(U4-NC-Pad1)") (class "Default")
      (node (ref "U4") (pin "1") (pinfunction "NC_1") (pintype "passive"))
    )
    (net (code "109") (name "unconnected-(U4-NC-Pad4)") (class "Default")
      (node (ref "U4") (pin "4") (pinfunction "NC_4") (pintype "passive"))
    )
    (net (code "110") (name "unconnected-(U5-NC-Pad1)") (class "Default")
      (node (ref "U5") (pin "1") (pinfunction "NC_1") (pintype "passive"))
    )
    (net (code "111") (name "unconnected-(U5-NC-Pad4)") (class "Default")
      (node (ref "U5") (pin "4") (pinfunction "NC_4") (pintype "passive"))
    )
    (net (code "112") (name "unconnected-(U6-NC-Pad1)") (class "Default")
      (node (ref "U6") (pin "1") (pinfunction "NC_1") (pintype "passive"))
    )
    (net (code "113") (name "unconnected-(U6-NC-Pad4)") (class "Default")
      (node (ref "U6") (pin "4") (pinfunction "NC_4") (pintype "passive"))
    )
    (net (code "114") (name "unconnected-(U8-O5-Pad10)") (class "Default")
      (node (ref "U8") (pin "10") (pinfunction "O5_10") (pintype "passive"))
    )
    (net (code "115") (name "unconnected-(U8-O6-Pad12)") (class "Default")
      (node (ref "U8") (pin "12") (pinfunction "O6_12") (pintype "passive"))
    )
    (net (code "116") (name "unconnected-(U9-NC-Pad73)") (class "Default")
      (node (ref "U9") (pin "73") (pinfunction "NC_73") (pintype "passive"))
    )
    (net (code "117") (name "unconnected-(U9-PA0{slash}WKUP{slash}U2_CTS{slash}ADC0{slash}T2C1_ETR{slash}T5C1{slash}T8_ETR-Pad23)") (class "Default")
      (node (ref "U9") (pin "23") (pinfunction "PA0/WKUP/U2_CTS/ADC0/T2C1_ETR/T5C1/T8_ETR_23") (pintype "passive"))
    )
    (net (code "118") (name "unconnected-(U9-PA1{slash}U2_RTS{slash}ADC1{slash}T2C2{slash}T5C2-Pad24)") (class "Default")
      (node (ref "U9") (pin "24") (pinfunction "PA1/U2_RTS/ADC1/T2C2/T5C2_24") (pintype "passive"))
    )
    (net (code "119") (name "unconnected-(U9-PA2{slash}U2_TX{slash}ADC2{slash}T2C3{slash}T5C3-Pad25)") (class "Default")
      (node (ref "U9") (pin "25") (pinfunction "PA2/U2_TX/ADC2/T2C3/T5C3_25") (pintype "passive"))
    )
    (net (code "120") (name "unconnected-(U9-PA3{slash}U2_RX{slash}ADC3{slash}T2C4{slash}T5C4-Pad26)") (class "Default")
      (node (ref "U9") (pin "26") (pinfunction "PA3/U2_RX/ADC3/T2C4/T5C4_26") (pintype "passive"))
    )
    (net (code "121") (name "unconnected-(U9-PA4{slash}SPI1_NSS{slash}U2_CK{slash}ADC4{slash}DAC1-Pad29)") (class "Default")
      (node (ref "U9") (pin "29") (pinfunction "PA4/SPI1_NSS/U2_CK/ADC4/DAC1_29") (pintype "passive"))
    )
    (net (code "122") (name "unconnected-(U9-PA5{slash}SPI1_SCK{slash}ADC5{slash}DAC2-Pad30)") (class "Default")
      (node (ref "U9") (pin "30") (pinfunction "PA5/SPI1_SCK/ADC5/DAC2_30") (pintype "passive"))
    )
    (net (code "123") (name "unconnected-(U9-PA6{slash}SPI1_MISO{slash}ADC6{slash}T3C1{slash}T8_BKIN-Pad31)") (class "Default")
      (node (ref "U9") (pin "31") (pinfunction "PA6/SPI1_MISO/ADC6/T3C1/T8_BKIN_31") (pintype "passive"))
    )
    (net (code "124") (name "unconnected-(U9-PA7{slash}SPI1_MOSI{slash}ADC7{slash}T3C2{slash}T8C1N-Pad32)") (class "Default")
      (node (ref "U9") (pin "32") (pinfunction "PA7/SPI1_MOSI/ADC7/T3C2/T8C1N_32") (pintype "passive"))
    )
    (net (code "125") (name "unconnected-(U9-PA11{slash}U1_CTS{slash}CAN_RX{slash}USBDM{slash}T1C4-Pad70)") (class "Default")
      (node (ref "U9") (pin "70") (pinfunction "PA11/U1_CTS/CAN_RX/USBDM/T1C4_70") (pintype "passive"))
    )
    (net (code "126") (name "unconnected-(U9-PA12{slash}U1_RTS{slash}CAN_TX{slash}USBDP{slash}TIM1_ETR-Pad71)") (class "Default")
      (node (ref "U9") (pin "71") (pinfunction "PA12/U1_RTS/CAN_TX/USBDP/TIM1_ETR_71") (pintype "passive"))
    )
    (net (code "127") (name "unconnected-(U9-PA15{slash}JTDI{slash}SPI3_NSS{slash}I2S3_WS-Pad77)") (class "Default")
      (node (ref "U9") (pin "77") (pinfunction "PA15/JTDI/SPI3_NSS/I2S3_WS_77") (pintype "passive"))
    )
    (net (code "128") (name "unconnected-(U9-PB3{slash}JTDO{slash}SPI3_SCK{slash}I2S3_CK-Pad89)") (class "Default")
      (node (ref "U9") (pin "89") (pinfunction "PB3/JTDO/SPI3_SCK/I2S3_CK_89") (pintype "passive"))
    )
    (net (code "129") (name "unconnected-(U9-PB4{slash}JNTRST{slash}SPI3_MISO-Pad90)") (class "Default")
      (node (ref "U9") (pin "90") (pinfunction "PB4/JNTRST/SPI3_MISO_90") (pintype "passive"))
    )
    (net (code "130") (name "unconnected-(U9-PB5{slash}I2C1_SMBA{slash}SPI3_MOSI{slash}I2S3_SD-Pad91)") (class "Default")
      (node (ref "U9") (pin "91") (pinfunction "PB5/I2C1_SMBA/SPI3_MOSI/I2S3_SD_91") (pintype "passive"))
    )
    (net (code "131") (name "unconnected-(U9-PB6{slash}I2C1_SCL{slash}T4C1-Pad92)") (class "Default")
      (node (ref "U9") (pin "92") (pinfunction "PB6/I2C1_SCL/T4C1_92") (pintype "passive"))
    )
    (net (code "132") (name "unconnected-(U9-PB7{slash}I2C1_SDA{slash}T4C2-Pad93)") (class "Default")
      (node (ref "U9") (pin "93") (pinfunction "PB7/I2C1_SDA/T4C2_93") (pintype "passive"))
    )
    (net (code "133") (name "unconnected-(U9-PB8{slash}T4C3{slash}SDIO_D4-Pad95)") (class "Default")
      (node (ref "U9") (pin "95") (pinfunction "PB8/T4C3/SDIO_D4_95") (pintype "passive"))
    )
    (net (code "134") (name "unconnected-(U9-PB9{slash}T4C4{slash}SDIO_D5-Pad96)") (class "Default")
      (node (ref "U9") (pin "96") (pinfunction "PB9/T4C4/SDIO_D5_96") (pintype "passive"))
    )
    (net (code "135") (name "unconnected-(U9-PB12{slash}SPI2_NSS{slash}I2S2_WS{slash}I2C2_SMBA{slash}TIM1_BKIN{slash}U3_CK-Pad51)") (class "Default")
      (node (ref "U9") (pin "51") (pinfunction "PB12/SPI2_NSS/I2S2_WS/I2C2_SMBA/TIM1_BKIN/U3_CK_51") (pintype "passive"))
    )
    (net (code "136") (name "unconnected-(U9-PC1{slash}ADC11-Pad16)") (class "Default")
      (node (ref "U9") (pin "16") (pinfunction "PC1/ADC11_16") (pintype "passive"))
    )
    (net (code "137") (name "unconnected-(U9-PC2{slash}ADC12-Pad17)") (class "Default")
      (node (ref "U9") (pin "17") (pinfunction "PC2/ADC12_17") (pintype "passive"))
    )
    (net (code "138") (name "unconnected-(U9-PC3{slash}ADC13-Pad18)") (class "Default")
      (node (ref "U9") (pin "18") (pinfunction "PC3/ADC13_18") (pintype "passive"))
    )
    (net (code "139") (name "unconnected-(U9-PC4{slash}ADC14-Pad33)") (class "Default")
      (node (ref "U9") (pin "33") (pinfunction "PC4/ADC14_33") (pintype "passive"))
    )
    (net (code "140") (name "unconnected-(U9-PC6{slash}I2S2_MCK{slash}T8C1{slash}SDIO_D6-Pad63)") (class "Default")
      (node (ref "U9") (pin "63") (pinfunction "PC6/I2S2_MCK/T8C1/SDIO_D6_63") (pintype "passive"))
    )
    (net (code "141") (name "unconnected-(U9-PC7{slash}I2S3_MCK{slash}T8C2{slash}SDIO_D7-Pad64)") (class "Default")
      (node (ref "U9") (pin "64") (pinfunction "PC7/I2S3_MCK/T8C2/SDIO_D7_64") (pintype "passive"))
    )
    (net (code "142") (name "unconnected-(U9-PC8{slash}T8C3{slash}SDIO_D0-Pad65)") (class "Default")
      (node (ref "U9") (pin "65") (pinfunction "PC8/T8C3/SDIO_D0_65") (pintype "passive"))
    )
    (net (code "143") (name "unconnected-(U9-PC9{slash}T8C4{slash}SDIO_D1-Pad66)") (class "Default")
      (node (ref "U9") (pin "66") (pinfunction "PC9/T8C4/SDIO_D1_66") (pintype "passive"))
    )
    (net (code "144") (name "unconnected-(U9-PC10{slash}U4_TX{slash}SDIO_D2-Pad78)") (class "Default")
      (node (ref "U9") (pin "78") (pinfunction "PC10/U4_TX/SDIO_D2_78") (pintype "passive"))
    )
    (net (code "145") (name "unconnected-(U9-PC11{slash}U4_RX{slash}SDIO_D3-Pad79)") (class "Default")
      (node (ref "U9") (pin "79") (pinfunction "PC11/U4_RX/SDIO_D3_79") (pintype "passive"))
    )
    (net (code "146") (name "unconnected-(U9-PC13{slash}TAMPER-RTC-Pad7)") (class "Default")
      (node (ref "U9") (pin "7") (pinfunction "PC13/TAMPER-RTC_7") (pintype "passive"))
    )
    (net (code "147") (name "unconnected-(U9-PD0{slash}OSCIN-Pad81)") (class "Default")
      (node (ref "U9") (pin "81") (pinfunction "PD0/OSCIN_81") (pintype "passive"))
    )
    (net (code "148") (name "unconnected-(U9-PD1{slash}OSCOUT-Pad82)") (class "Default")
      (node (ref "U9") (pin "82") (pinfunction "PD1/OSCOUT_82") (pintype "passive"))
    )
    (net (code "149") (name "unconnected-(U9-PD2{slash}TIM3_ETR{slash}U5_RX{slash}SDIO_CMD-Pad83)") (class "Default")
      (node (ref "U9") (pin "83") (pinfunction "PD2/TIM3_ETR/U5_RX/SDIO_CMD_83") (pintype "passive"))
    )
    (net (code "150") (name "unconnected-(U9-PD3-Pad84)") (class "Default")
      (node (ref "U9") (pin "84") (pinfunction "PD3_84") (pintype "passive"))
    )
    (net (code "151") (name "unconnected-(U9-PD4-Pad85)") (class "Default")
      (node (ref "U9") (pin "85") (pinfunction "PD4_85") (pintype "passive"))
    )
    (net (code "152") (name "unconnected-(U9-PD5-Pad86)") (class "Default")
      (node (ref "U9") (pin "86") (pinfunction "PD5_86") (pintype "passive"))
    )
    (net (code "153") (name "unconnected-(U9-PD6-Pad87)") (class "Default")
      (node (ref "U9") (pin "87") (pinfunction "PD6_87") (pintype "passive"))
    )
    (net (code "154") (name "unconnected-(U9-PD7-Pad88)") (class "Default")
      (node (ref "U9") (pin "88") (pinfunction "PD7_88") (pintype "passive"))
    )
    (net (code "155") (name "unconnected-(U9-PD8-Pad55)") (class "Default")
      (node (ref "U9") (pin "55") (pinfunction "PD8_55") (pintype "passive"))
    )
    (net (code "156") (name "unconnected-(U9-PD9-Pad56)") (class "Default")
      (node (ref "U9") (pin "56") (pinfunction "PD9_56") (pintype "passive"))
    )
    (net (code "157") (name "unconnected-(U9-PD10-Pad57)") (class "Default")
      (node (ref "U9") (pin "57") (pinfunction "PD10_57") (pintype "passive"))
    )
    (net (code "158") (name "unconnected-(U9-PD11-Pad58)") (class "Default")
      (node (ref "U9") (pin "58") (pinfunction "PD11_58") (pintype "passive"))
    )
    (net (code "159") (name "unconnected-(U9-PD12-Pad59)") (class "Default")
      (node (ref "U9") (pin "59") (pinfunction "PD12_59") (pintype "passive"))
    )
    (net (code "160") (name "unconnected-(U9-PD13-Pad60)") (class "Default")
      (node (ref "U9") (pin "60") (pinfunction "PD13_60") (pintype "passive"))
    )
    (net (code "161") (name "unconnected-(U9-PD14-Pad61)") (class "Default")
      (node (ref "U9") (pin "61") (pinfunction "PD14_61") (pintype "passive"))
    )
    (net (code "162") (name "unconnected-(U9-PD15-Pad62)") (class "Default")
      (node (ref "U9") (pin "62") (pinfunction "PD15_62") (pintype "passive"))
    )
    (net (code "163") (name "unconnected-(U9-PE0{slash}T4_ETR-Pad97)") (class "Default")
      (node (ref "U9") (pin "97") (pinfunction "PE0/T4_ETR_97") (pintype "passive"))
    )
    (net (code "164") (name "unconnected-(U9-PE3-Pad2)") (class "Default")
      (node (ref "U9") (pin "2") (pinfunction "PE3_2") (pintype "passive"))
    )
    (net (code "165") (name "unconnected-(U9-PE4-Pad3)") (class "Default")
      (node (ref "U9") (pin "3") (pinfunction "PE4_3") (pintype "passive"))
    )
    (net (code "166") (name "unconnected-(U9-PE5-Pad4)") (class "Default")
      (node (ref "U9") (pin "4") (pinfunction "PE5_4") (pintype "passive"))
    )
    (net (code "167") (name "unconnected-(U9-PE6-Pad5)") (class "Default")
      (node (ref "U9") (pin "5") (pinfunction "PE6_5") (pintype "passive"))
    )
    (net (code "168") (name "unconnected-(U9-PE10-Pad41)") (class "Default")
      (node (ref "U9") (pin "41") (pinfunction "PE10_41") (pintype "passive"))
    )
    (net (code "169") (name "unconnected-(U9-PE11-Pad42)") (class "Default")
      (node (ref "U9") (pin "42") (pinfunction "PE11_42") (pintype "passive"))
    )
    (net (code "170") (name "unconnected-(U9-PE12-Pad43)") (class "Default")
      (node (ref "U9") (pin "43") (pinfunction "PE12_43") (pintype "passive"))
    )
    (net (code "171") (name "unconnected-(U9-PE13-Pad44)") (class "Default")
      (node (ref "U9") (pin "44") (pinfunction "PE13_44") (pintype "passive"))
    )
    (net (code "172") (name "unconnected-(U9-PE14-Pad45)") (class "Default")
      (node (ref "U9") (pin "45") (pinfunction "PE14_45") (pintype "passive"))
    )
    (net (code "173") (name "unconnected-(U9-PE15-Pad46)") (class "Default")
      (node (ref "U9") (pin "46") (pinfunction "PE15_46") (pintype "passive"))
    )
  )
)
